# Tartarus_Joystick_Mod_M0.net
KiCad netlist of a schematic drawn in Altium Designer
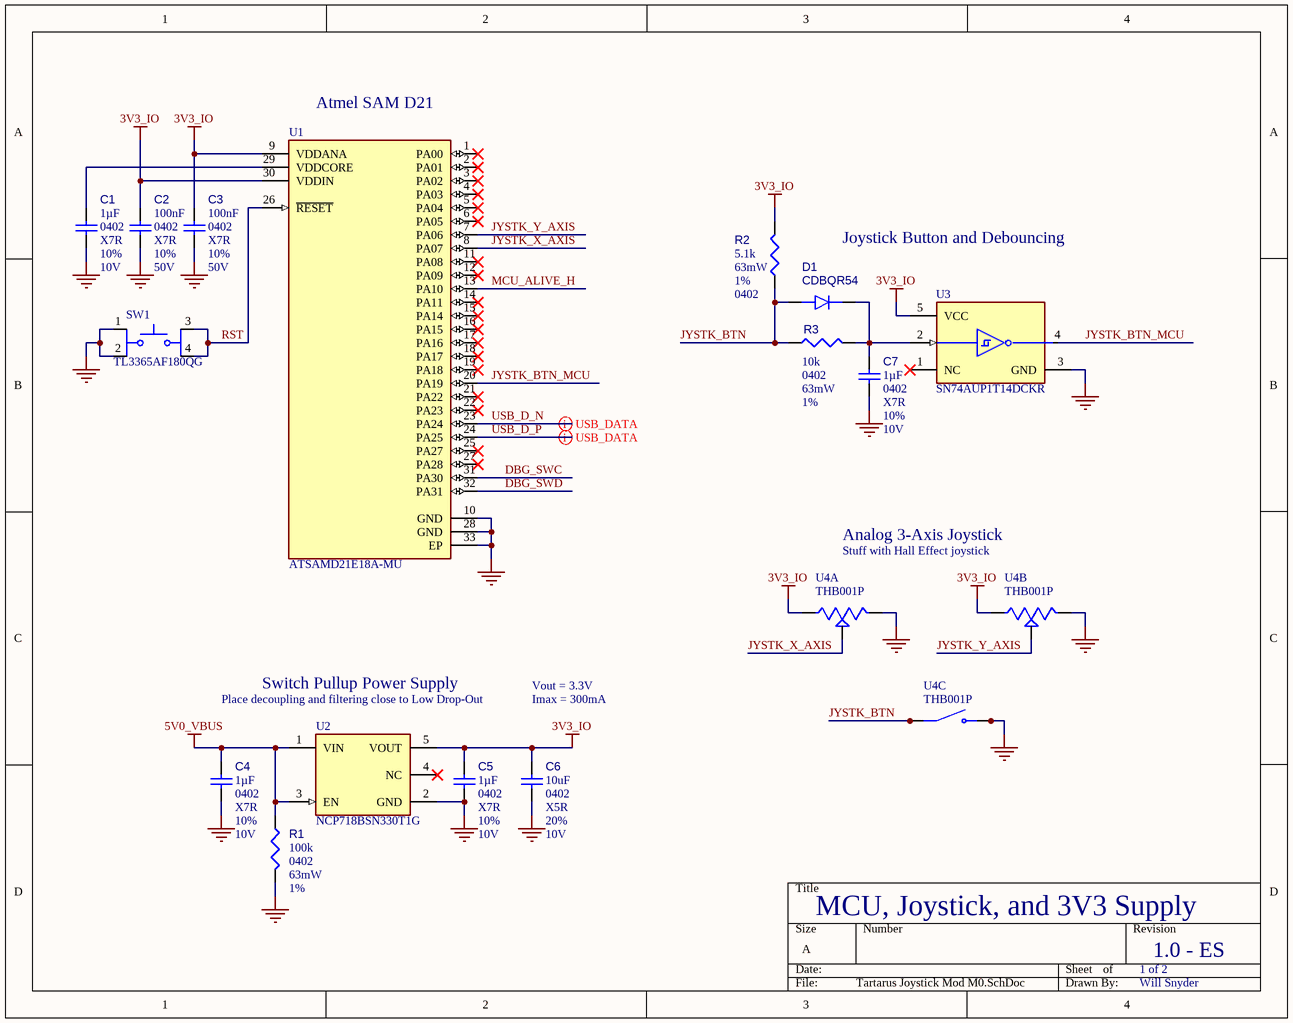
[diagram p0: Tartarus Joystick Mod M0.SchDoc]

(export (version "E")
  (design (tool "Eeschema 10.0.6"))
  (components
    (comp (ref "C1")
      (value "1µF")
      (footprint "CAPC1005X55X30NL05T10")
      (fields
        (field (name "CASE/PACKAGE") "0402")
        (field (name "VOLTAGE RATING") "10V")
        (field (name "CAPACITOR TYPE") "X7R")
        (field (name "TOLERANCE") "10%")
        (field (name "Comment") "GRM155Z71A105KE01D")
      )
      (libsource (lib "Personal Workspace") (part "CAP-NP-2"))
    )
    (comp (ref "C2")
      (value "100nF")
      (footprint "CAPC1005X55X30NL05T10")
      (fields
        (field (name "VOLTAGE RATING") "50V")
        (field (name "CAPACITOR TYPE") "X7R")
        (field (name "CASE/PACKAGE") "0402")
        (field (name "TOLERANCE") "10%")
        (field (name "Comment") "04025C104KAT4A")
      )
      (libsource (lib "Personal Workspace") (part "CAP-NP-2"))
    )
    (comp (ref "C3")
      (value "100nF")
      (footprint "CAPC1005X55X30NL05T10")
      (fields
        (field (name "VOLTAGE RATING") "50V")
        (field (name "CAPACITOR TYPE") "X7R")
        (field (name "CASE/PACKAGE") "0402")
        (field (name "TOLERANCE") "10%")
        (field (name "Comment") "04025C104KAT4A")
      )
      (libsource (lib "Personal Workspace") (part "CAP-NP-2"))
    )
    (comp (ref "C4")
      (value "1µF")
      (footprint "CAPC1005X55X30NL05T10")
      (fields
        (field (name "CASE/PACKAGE") "0402")
        (field (name "VOLTAGE RATING") "10V")
        (field (name "CAPACITOR TYPE") "X7R")
        (field (name "TOLERANCE") "10%")
        (field (name "Comment") "GRM155Z71A105KE01D")
      )
      (libsource (lib "Personal Workspace") (part "CAP-NP-2"))
    )
    (comp (ref "C5")
      (value "1µF")
      (footprint "CAPC1005X55X30NL05T10")
      (fields
        (field (name "CASE/PACKAGE") "0402")
        (field (name "VOLTAGE RATING") "10V")
        (field (name "CAPACITOR TYPE") "X7R")
        (field (name "TOLERANCE") "10%")
        (field (name "Comment") "GRM155Z71A105KE01D")
      )
      (libsource (lib "Personal Workspace") (part "CAP-NP-2"))
    )
    (comp (ref "C6")
      (value "10uF")
      (footprint "CAPC1005X55X30NL05T10")
      (fields
        (field (name "CAPACITOR TYPE") "X5R")
        (field (name "VOLTAGE RATING") "10V")
        (field (name "TOLERANCE") "20%")
        (field (name "CASE/PACKAGE") "0402")
        (field (name "Comment") "GRM155R61A106ME11J")
      )
      (libsource (lib "Personal Workspace") (part "CAP-NP-2"))
    )
    (comp (ref "C7")
      (value "1µF")
      (footprint "CAPC1005X55X30NL05T10")
      (fields
        (field (name "CASE/PACKAGE") "0402")
        (field (name "VOLTAGE RATING") "10V")
        (field (name "CAPACITOR TYPE") "X7R")
        (field (name "TOLERANCE") "10%")
        (field (name "Comment") "GRM155Z71A105KE01D")
      )
      (libsource (lib "Personal Workspace") (part "CAP-NP-2"))
    )
    (comp (ref "D1")
      (value "CDBQR54")
      (footprint "Chip2PinSM127P600-8N")
      (description "Rectifier Diode, Schottky, 1 Phase, 1 Element, 0.2A, 30V V(RRM), Silicon")
      (libsource (lib "Personal Workspace") (part "DIODE-2"))
    )
    (comp (ref "R1")
      (value "100k")
      (footprint "RESC0402(1005)_L")
      (description "100K 0.063W 1% 0402 (1005 Metric)  SMD")
      (fields
        (field (name "POWER") "63mW")
        (field (name "CASE/PACKAGE") "0402")
        (field (name "TOLERANCE") "1%")
        (field (name "Comment") "100KR2F")
      )
      (libsource (lib "Personal Workspace") (part "100KR2F"))
    )
    (comp (ref "R2")
      (value "5.1k")
      (footprint "RESC1005X40X25NL05T05")
      (description "Fixed Resistor, Thin Film, 0.063W, 5100ohm, 50V, 1% +/-Tol, 50ppm/Cel, Surface Mount, 0402")
      (fields
        (field (name "POWER") "63mW")
        (field (name "TOLERANCE") "1%")
        (field (name "CASE/PACKAGE") "0402")
        (field (name "Comment") "MCS04020C5101FE000")
      )
      (libsource (lib "Personal Workspace") (part "RES-2"))
    )
    (comp (ref "R3")
      (value "10k")
      (footprint "RESC1005X40X25NL05T05")
      (description "Fixed Resistor, Thin Film, 0.063W, 22000ohm, 50V, 1% +/-Tol, 50ppm/Cel, Surface Mount, 0402")
      (fields
        (field (name "POWER") "63mW")
        (field (name "TOLERANCE") "1%")
        (field (name "MOUNTING TECHNOLOGY") "0402")
        (field (name "Comment") "MCS04020C2202FE000")
      )
      (libsource (lib "Personal Workspace") (part "RES-2"))
    )
    (comp (ref "SW1")
      (value "TL3365AF180QG")
      (footprint "SW_TL3365AF180QG")
      (description "Tactile Switch SPST-NO Top Actuated Surface Mount")
      (fields (field (name "MF") "E-Switch"))
      (libsource (lib "Personal Workspace") (part "TL3365AF180QG"))
    )
    (comp (ref "U1")
      (value "ATSAMD21E18A-MU")
      (footprint "FP-PG-IPC_A")
      (description "RISC Microcontroller, 32-Bit, FLASH, CORTEX-M0 CPU, 48MHz, CMOS")
      (libsource (lib "Personal Workspace") (part "079772c84f40789a0aafecd75ebb365"))
    )
    (comp (ref "U2")
      (value "NCP718BSN330T1G")
      (footprint "SOT95P280X100-5N")
      (description "Fixed Positive LDO Regulator, 3.3V, 440V Dropout, PDSO5")
      (libsource (lib "Personal Workspace") (part "96048095611b4a9579e1e315950d302"))
    )
    (comp (ref "U3")
      (value "SN74AUP1T14DCKR")
      (footprint "FP-DCK0005A-IPC_B")
      (description "Inverter, AUP/ULP/V Series, 1-Func, 1-Input, CMOS, PDSO5")
      (libsource (lib "Personal Workspace") (part "4b38496dcb848226add7bafd17519af"))
    )
    (comp (ref "U4")
      (value "THB001P")
      (footprint "CNK_THB001P")
      (description "Joystick, 2 - Axis Analog (Resistive) Output")
      (fields (field (name "MF") "C&K"))
      (libsource (lib "Personal Workspace") (part "THB001P"))
    )
  )
  (nets
    (net (code "1") (name "/DBG_SWC") (class "Default")
      (node (ref "U1") (pin "31") (pinfunction "PA30_31") (pintype "bidirectional"))
    )
    (net (code "2") (name "/DBG_SWD") (class "Default")
      (node (ref "U1") (pin "32") (pinfunction "PA31_32") (pintype "bidirectional"))
    )
    (net (code "3") (name "/JYSTK_BTN") (class "Default")
      (node (ref "D1") (pin "2") (pinfunction "A_2") (pintype "passive"))
      (node (ref "R2") (pin "1") (pinfunction "1_1") (pintype "passive"))
      (node (ref "R3") (pin "1") (pinfunction "1_1") (pintype "passive"))
      (node (ref "U4") (pin "C") (pinfunction "COM_C") (pintype "passive"))
      (node (ref "U4") (pin "D") (pinfunction "COM_D") (pintype "passive"))
    )
    (net (code "4") (name "/JYSTK_BTN_MCU") (class "Default")
      (node (ref "U1") (pin "20") (pinfunction "PA19_20") (pintype "bidirectional"))
      (node (ref "U3") (pin "4") (pinfunction "Y_4") (pintype "output"))
    )
    (net (code "5") (name "/JYSTK_X_AXIS") (class "Default")
      (node (ref "U1") (pin "8") (pinfunction "PA07_8") (pintype "bidirectional"))
      (node (ref "U4") (pin "VR1_2") (pinfunction "VR1_2_VR1_2") (pintype "passive"))
    )
    (net (code "6") (name "/JYSTK_Y_AXIS") (class "Default")
      (node (ref "U1") (pin "7") (pinfunction "PA06_7") (pintype "bidirectional"))
      (node (ref "U4") (pin "VR2_2") (pinfunction "VR2_2_VR2_2") (pintype "passive"))
    )
    (net (code "7") (name "/MCU_ALIVE_H") (class "Default")
      (node (ref "U1") (pin "13") (pinfunction "PA10_13") (pintype "bidirectional"))
    )
    (net (code "8") (name "/RST") (class "Default")
      (node (ref "SW1") (pin "3") (pinfunction "3_3") (pintype "passive"))
      (node (ref "SW1") (pin "4") (pinfunction "4_4") (pintype "passive"))
      (node (ref "U1") (pin "26") (pinfunction "~{RESET}_26") (pintype "input"))
    )
    (net (code "9") (name "/USB_D_N") (class "Default")
      (node (ref "U1") (pin "23") (pinfunction "PA24_23") (pintype "bidirectional"))
    )
    (net (code "10") (name "/USB_D_P") (class "Default")
      (node (ref "U1") (pin "24") (pinfunction "PA25_24") (pintype "bidirectional"))
    )
    (net (code "11") (name "3V3_IO") (class "Default")
      (node (ref "C2") (pin "1") (pinfunction "1_1") (pintype "passive"))
      (node (ref "C3") (pin "1") (pinfunction "1_1") (pintype "passive"))
      (node (ref "C5") (pin "1") (pinfunction "1_1") (pintype "passive"))
      (node (ref "C6") (pin "1") (pinfunction "1_1") (pintype "passive"))
      (node (ref "R2") (pin "2") (pinfunction "2_2") (pintype "passive"))
      (node (ref "U1") (pin "30") (pinfunction "VDDIN_30") (pintype "power_in"))
      (node (ref "U1") (pin "9") (pinfunction "VDDANA_9") (pintype "power_in"))
      (node (ref "U2") (pin "5") (pinfunction "VOUT_5") (pintype "power_in"))
      (node (ref "U3") (pin "5") (pinfunction "VCC_5") (pintype "power_in"))
      (node (ref "U4") (pin "VR1_1") (pinfunction "VR1_1_VR1_1") (pintype "passive"))
      (node (ref "U4") (pin "VR2_1") (pinfunction "VR2_1_VR2_1") (pintype "passive"))
    )
    (net (code "12") (name "5V0_VBUS") (class "Default")
      (node (ref "C4") (pin "1") (pinfunction "1_1") (pintype "passive"))
      (node (ref "R1") (pin "1") (pinfunction "1_1") (pintype "passive"))
      (node (ref "U2") (pin "1") (pinfunction "VIN_1") (pintype "power_in"))
      (node (ref "U2") (pin "3") (pinfunction "EN_3") (pintype "input"))
    )
    (net (code "13") (name "GND") (class "Default")
      (node (ref "C1") (pin "2") (pinfunction "2_2") (pintype "passive"))
      (node (ref "C2") (pin "2") (pinfunction "2_2") (pintype "passive"))
      (node (ref "C3") (pin "2") (pinfunction "2_2") (pintype "passive"))
      (node (ref "C4") (pin "2") (pinfunction "2_2") (pintype "passive"))
      (node (ref "C5") (pin "2") (pinfunction "2_2") (pintype "passive"))
      (node (ref "C6") (pin "2") (pinfunction "2_2") (pintype "passive"))
      (node (ref "C7") (pin "2") (pinfunction "2_2") (pintype "passive"))
      (node (ref "R1") (pin "2") (pinfunction "2_2") (pintype "passive"))
      (node (ref "SW1") (pin "1") (pinfunction "1_1") (pintype "passive"))
      (node (ref "SW1") (pin "2") (pinfunction "2_2") (pintype "passive"))
      (node (ref "U1") (pin "10") (pinfunction "GND_10") (pintype "power_in"))
      (node (ref "U1") (pin "28") (pinfunction "GND_28") (pintype "power_in"))
      (node (ref "U1") (pin "33") (pinfunction "EP_33") (pintype "power_in"))
      (node (ref "U2") (pin "2") (pinfunction "GND_2") (pintype "power_in"))
      (node (ref "U3") (pin "3") (pinfunction "GND_3") (pintype "power_in"))
      (node (ref "U4") (pin "A") (pinfunction "NO_A") (pintype "passive"))
      (node (ref "U4") (pin "B") (pinfunction "NO_B") (pintype "passive"))
      (node (ref "U4") (pin "VR1_3") (pinfunction "VR1_3_VR1_3") (pintype "passive"))
      (node (ref "U4") (pin "VR2_3") (pinfunction "VR2_3_VR2_3") (pintype "passive"))
    )
    (net (code "14") (name "Net-(D1-K)") (class "Default")
      (node (ref "C7") (pin "1") (pinfunction "1_1") (pintype "passive"))
      (node (ref "D1") (pin "1") (pinfunction "K_1") (pintype "passive"))
      (node (ref "R3") (pin "2") (pinfunction "2_2") (pintype "passive"))
      (node (ref "U3") (pin "2") (pinfunction "A_2") (pintype "input"))
    )
    (net (code "15") (name "Net-(U1-VDDCORE)") (class "Default")
      (node (ref "C1") (pin "1") (pinfunction "1_1") (pintype "passive"))
      (node (ref "U1") (pin "29") (pinfunction "VDDCORE_29") (pintype "power_in"))
    )
    (net (code "16") (name "unconnected-(U1-PA00-Pad1)") (class "Default")
      (node (ref "U1") (pin "1") (pinfunction "PA00_1") (pintype "bidirectional+no_connect"))
    )
    (net (code "17") (name "unconnected-(U1-PA01-Pad2)") (class "Default")
      (node (ref "U1") (pin "2") (pinfunction "PA01_2") (pintype "bidirectional+no_connect"))
    )
    (net (code "18") (name "unconnected-(U1-PA02-Pad3)") (class "Default")
      (node (ref "U1") (pin "3") (pinfunction "PA02_3") (pintype "bidirectional+no_connect"))
    )
    (net (code "19") (name "unconnected-(U1-PA03-Pad4)") (class "Default")
      (node (ref "U1") (pin "4") (pinfunction "PA03_4") (pintype "bidirectional+no_connect"))
    )
    (net (code "20") (name "unconnected-(U1-PA04-Pad5)") (class "Default")
      (node (ref "U1") (pin "5") (pinfunction "PA04_5") (pintype "bidirectional+no_connect"))
    )
    (net (code "21") (name "unconnected-(U1-PA05-Pad6)") (class "Default")
      (node (ref "U1") (pin "6") (pinfunction "PA05_6") (pintype "bidirectional+no_connect"))
    )
    (net (code "22") (name "unconnected-(U1-PA08-Pad11)") (class "Default")
      (node (ref "U1") (pin "11") (pinfunction "PA08_11") (pintype "bidirectional+no_connect"))
    )
    (net (code "23") (name "unconnected-(U1-PA09-Pad12)") (class "Default")
      (node (ref "U1") (pin "12") (pinfunction "PA09_12") (pintype "bidirectional+no_connect"))
    )
    (net (code "24") (name "unconnected-(U1-PA11-Pad14)") (class "Default")
      (node (ref "U1") (pin "14") (pinfunction "PA11_14") (pintype "bidirectional+no_connect"))
    )
    (net (code "25") (name "unconnected-(U1-PA14-Pad15)") (class "Default")
      (node (ref "U1") (pin "15") (pinfunction "PA14_15") (pintype "bidirectional+no_connect"))
    )
    (net (code "26") (name "unconnected-(U1-PA15-Pad16)") (class "Default")
      (node (ref "U1") (pin "16") (pinfunction "PA15_16") (pintype "bidirectional+no_connect"))
    )
    (net (code "27") (name "unconnected-(U1-PA16-Pad17)") (class "Default")
      (node (ref "U1") (pin "17") (pinfunction "PA16_17") (pintype "bidirectional+no_connect"))
    )
    (net (code "28") (name "unconnected-(U1-PA17-Pad18)") (class "Default")
      (node (ref "U1") (pin "18") (pinfunction "PA17_18") (pintype "bidirectional+no_connect"))
    )
    (net (code "29") (name "unconnected-(U1-PA18-Pad19)") (class "Default")
      (node (ref "U1") (pin "19") (pinfunction "PA18_19") (pintype "bidirectional+no_connect"))
    )
    (net (code "30") (name "unconnected-(U1-PA22-Pad21)") (class "Default")
      (node (ref "U1") (pin "21") (pinfunction "PA22_21") (pintype "bidirectional+no_connect"))
    )
    (net (code "31") (name "unconnected-(U1-PA23-Pad22)") (class "Default")
      (node (ref "U1") (pin "22") (pinfunction "PA23_22") (pintype "bidirectional+no_connect"))
    )
    (net (code "32") (name "unconnected-(U1-PA27-Pad25)") (class "Default")
      (node (ref "U1") (pin "25") (pinfunction "PA27_25") (pintype "bidirectional+no_connect"))
    )
    (net (code "33") (name "unconnected-(U1-PA28-Pad27)") (class "Default")
      (node (ref "U1") (pin "27") (pinfunction "PA28_27") (pintype "bidirectional+no_connect"))
    )
    (net (code "34") (name "unconnected-(U2-NC-Pad4)") (class "Default")
      (node (ref "U2") (pin "4") (pinfunction "NC_4") (pintype "passive+no_connect"))
    )
    (net (code "35") (name "unconnected-(U3-NC-Pad1)") (class "Default")
      (node (ref "U3") (pin "1") (pinfunction "NC_1") (pintype "passive+no_connect"))
    )
  )
)
